# 08_FPGA.net
KiCad netlist of a schematic drawn in Altium Designer
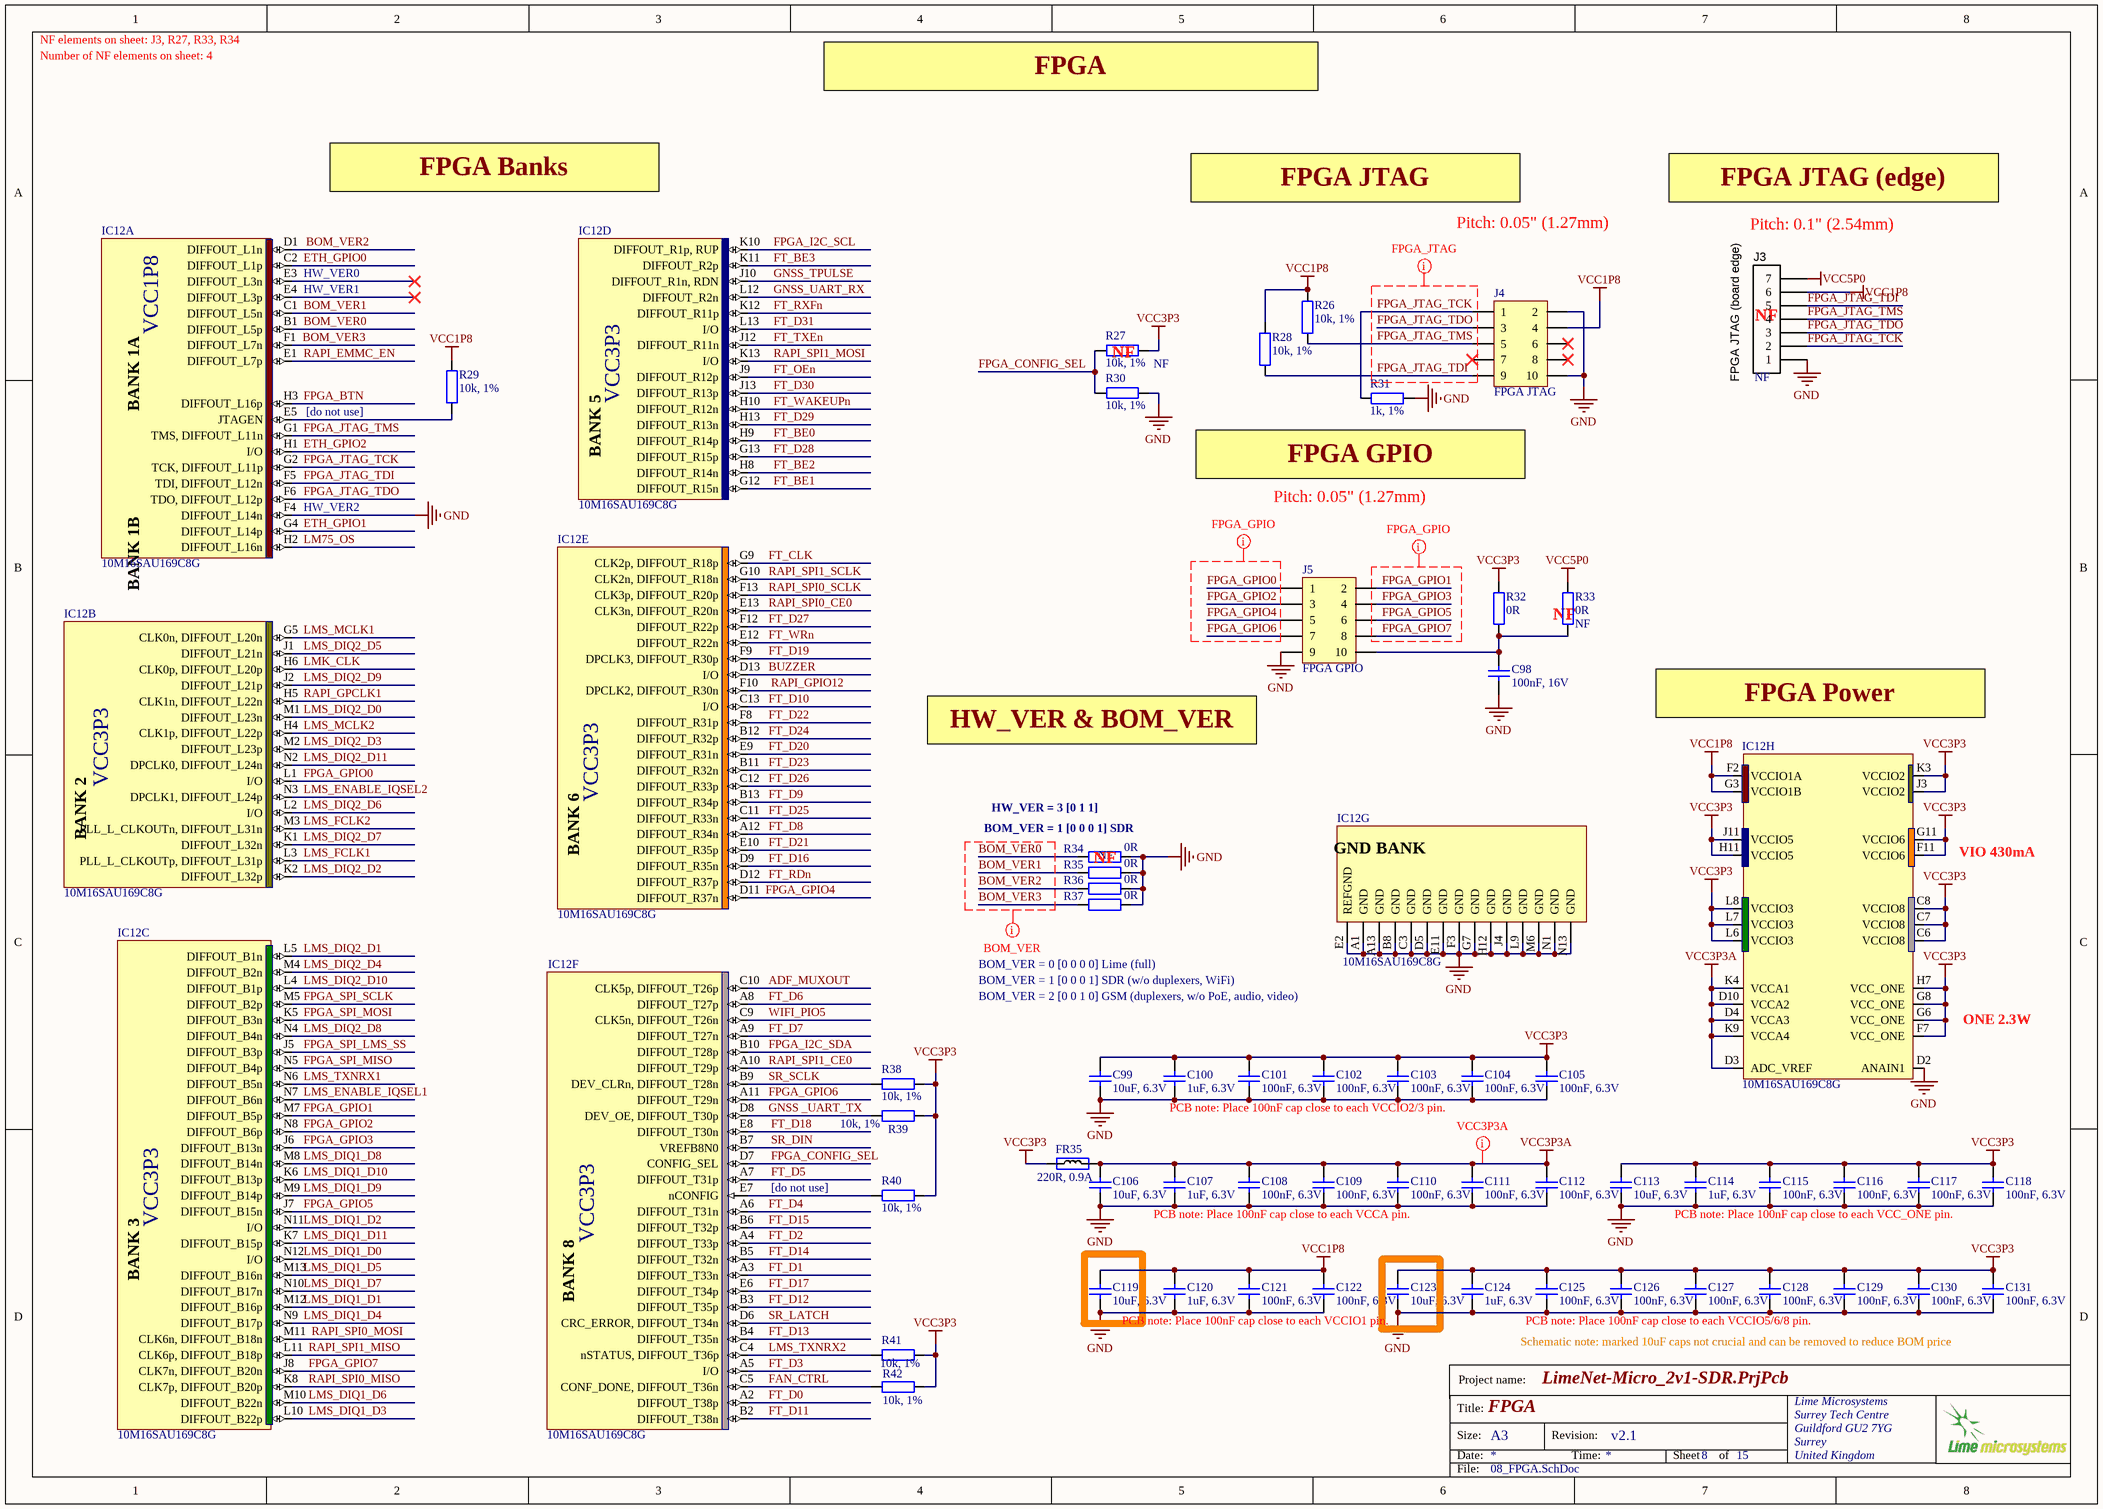
[diagram p0: 08_FPGA.SchDoc]

(export (version "E")
  (design (tool "Eeschema 10.0.6"))
  (components
    (comp (ref "C98")
      (value "100nF, 16V")
      (footprint "CAP0402")
      (fields
        (field (name "MANUFACTURER") "Murata Electronics")
        (field (name "TOLERANCE") "10 %")
        (field (name "MANUFACTURER PART NUMBER") "GRM155R71C104KA88D")
      )
      (libsource (lib "LimeMicroAltiumLib_schLib") (part "Cap_0402"))
    )
    (comp (ref "C99")
      (value "10uF, 6.3V")
      (footprint "CAP0603")
      (fields (field (name "TOLERANCE") "±20%") (field (name "MANUFACTURER") "Yageo"))
      (libsource (lib "LimeFPGAboard_schLib") (part "Cap_0603"))
    )
    (comp (ref "C100")
      (value "1uF, 6.3V")
      (footprint "CAP0201")
      (fields (field (name "TOLERANCE") "±20%") (field (name "MANUFACTURER") "TDK Corporation"))
      (libsource (lib "LimeMicroAltiumLib_schLib") (part "Cap_0402"))
    )
    (comp (ref "C101")
      (value "100nF, 6.3V")
      (footprint "CAP0201")
      (fields (field (name "MANUFACTURER") "Murata") (field (name "TOLERANCE") "10 %"))
      (libsource (lib "LimeMicroAltiumLib_schLib") (part "Cap_0402"))
    )
    (comp (ref "C102")
      (value "100nF, 6.3V")
      (footprint "CAP0201")
      (fields (field (name "MANUFACTURER") "Murata") (field (name "TOLERANCE") "10 %"))
      (libsource (lib "LimeMicroAltiumLib_schLib") (part "Cap_0402"))
    )
    (comp (ref "C103")
      (value "100nF, 6.3V")
      (footprint "CAP0201")
      (fields (field (name "MANUFACTURER") "Murata") (field (name "TOLERANCE") "10 %"))
      (libsource (lib "LimeMicroAltiumLib_schLib") (part "Cap_0402"))
    )
    (comp (ref "C104")
      (value "100nF, 6.3V")
      (footprint "CAP0201")
      (fields (field (name "MANUFACTURER") "Murata") (field (name "TOLERANCE") "10 %"))
      (libsource (lib "LimeMicroAltiumLib_schLib") (part "Cap_0402"))
    )
    (comp (ref "C105")
      (value "100nF, 6.3V")
      (footprint "CAP0201")
      (fields (field (name "MANUFACTURER") "Murata") (field (name "TOLERANCE") "10 %"))
      (libsource (lib "LimeMicroAltiumLib_schLib") (part "Cap_0402"))
    )
    (comp (ref "C106")
      (value "10uF, 6.3V")
      (footprint "CAP0603")
      (fields (field (name "TOLERANCE") "±20%") (field (name "MANUFACTURER") "Yageo"))
      (libsource (lib "LimeFPGAboard_schLib") (part "Cap_0603"))
    )
    (comp (ref "C107")
      (value "1uF, 6.3V")
      (footprint "CAP0201")
      (fields (field (name "TOLERANCE") "±20%") (field (name "MANUFACTURER") "TDK Corporation"))
      (libsource (lib "LimeMicroAltiumLib_schLib") (part "Cap_0402"))
    )
    (comp (ref "C108")
      (value "100nF, 6.3V")
      (footprint "CAP0201")
      (fields (field (name "MANUFACTURER") "Murata") (field (name "TOLERANCE") "10 %"))
      (libsource (lib "LimeMicroAltiumLib_schLib") (part "Cap_0402"))
    )
    (comp (ref "C109")
      (value "100nF, 6.3V")
      (footprint "CAP0201")
      (fields (field (name "MANUFACTURER") "Murata") (field (name "TOLERANCE") "10 %"))
      (libsource (lib "LimeMicroAltiumLib_schLib") (part "Cap_0402"))
    )
    (comp (ref "C110")
      (value "100nF, 6.3V")
      (footprint "CAP0201")
      (fields (field (name "MANUFACTURER") "Murata") (field (name "TOLERANCE") "10 %"))
      (libsource (lib "LimeMicroAltiumLib_schLib") (part "Cap_0402"))
    )
    (comp (ref "C111")
      (value "100nF, 6.3V")
      (footprint "CAP0201")
      (fields (field (name "MANUFACTURER") "Murata") (field (name "TOLERANCE") "10 %"))
      (libsource (lib "LimeMicroAltiumLib_schLib") (part "Cap_0402"))
    )
    (comp (ref "C112")
      (value "100nF, 6.3V")
      (footprint "CAP0201")
      (fields (field (name "MANUFACTURER") "Murata") (field (name "TOLERANCE") "10 %"))
      (libsource (lib "LimeMicroAltiumLib_schLib") (part "Cap_0402"))
    )
    (comp (ref "C113")
      (value "10uF, 6.3V")
      (footprint "CAP0603")
      (fields (field (name "TOLERANCE") "±20%") (field (name "MANUFACTURER") "Yageo"))
      (libsource (lib "LimeFPGAboard_schLib") (part "Cap_0603"))
    )
    (comp (ref "C114")
      (value "1uF, 6.3V")
      (footprint "CAP0201")
      (fields (field (name "TOLERANCE") "±20%") (field (name "MANUFACTURER") "TDK Corporation"))
      (libsource (lib "LimeMicroAltiumLib_schLib") (part "Cap_0402"))
    )
    (comp (ref "C115")
      (value "100nF, 6.3V")
      (footprint "CAP0201")
      (fields (field (name "MANUFACTURER") "Murata") (field (name "TOLERANCE") "10 %"))
      (libsource (lib "LimeMicroAltiumLib_schLib") (part "Cap_0402"))
    )
    (comp (ref "C116")
      (value "100nF, 6.3V")
      (footprint "CAP0201")
      (fields (field (name "MANUFACTURER") "Murata") (field (name "TOLERANCE") "10 %"))
      (libsource (lib "LimeMicroAltiumLib_schLib") (part "Cap_0402"))
    )
    (comp (ref "C117")
      (value "100nF, 6.3V")
      (footprint "CAP0201")
      (fields (field (name "MANUFACTURER") "Murata") (field (name "TOLERANCE") "10 %"))
      (libsource (lib "LimeMicroAltiumLib_schLib") (part "Cap_0402"))
    )
    (comp (ref "C118")
      (value "100nF, 6.3V")
      (footprint "CAP0201")
      (fields (field (name "MANUFACTURER") "Murata") (field (name "TOLERANCE") "10 %"))
      (libsource (lib "LimeMicroAltiumLib_schLib") (part "Cap_0402"))
    )
    (comp (ref "C119")
      (value "10uF, 6.3V")
      (footprint "CAP0603")
      (fields (field (name "TOLERANCE") "±20%") (field (name "MANUFACTURER") "Yageo"))
      (libsource (lib "LimeFPGAboard_schLib") (part "Cap_0603"))
    )
    (comp (ref "C120")
      (value "1uF, 6.3V")
      (footprint "CAP0201")
      (fields (field (name "TOLERANCE") "±20%") (field (name "MANUFACTURER") "TDK Corporation"))
      (libsource (lib "LimeMicroAltiumLib_schLib") (part "Cap_0402"))
    )
    (comp (ref "C121")
      (value "100nF, 6.3V")
      (footprint "CAP0201")
      (fields (field (name "MANUFACTURER") "Murata") (field (name "TOLERANCE") "10 %"))
      (libsource (lib "LimeMicroAltiumLib_schLib") (part "Cap_0402"))
    )
    (comp (ref "C122")
      (value "100nF, 6.3V")
      (footprint "CAP0201")
      (fields (field (name "MANUFACTURER") "Murata") (field (name "TOLERANCE") "10 %"))
      (libsource (lib "LimeMicroAltiumLib_schLib") (part "Cap_0402"))
    )
    (comp (ref "C123")
      (value "10uF, 6.3V")
      (footprint "CAP0603")
      (fields (field (name "TOLERANCE") "±20%") (field (name "MANUFACTURER") "Yageo"))
      (libsource (lib "LimeFPGAboard_schLib") (part "Cap_0603"))
    )
    (comp (ref "C124")
      (value "1uF, 6.3V")
      (footprint "CAP0201")
      (fields (field (name "TOLERANCE") "±20%") (field (name "MANUFACTURER") "TDK Corporation"))
      (libsource (lib "LimeMicroAltiumLib_schLib") (part "Cap_0402"))
    )
    (comp (ref "C125")
      (value "100nF, 6.3V")
      (footprint "CAP0201")
      (fields (field (name "MANUFACTURER") "Murata") (field (name "TOLERANCE") "10 %"))
      (libsource (lib "LimeMicroAltiumLib_schLib") (part "Cap_0402"))
    )
    (comp (ref "C126")
      (value "100nF, 6.3V")
      (footprint "CAP0201")
      (fields (field (name "MANUFACTURER") "Murata") (field (name "TOLERANCE") "10 %"))
      (libsource (lib "LimeMicroAltiumLib_schLib") (part "Cap_0402"))
    )
    (comp (ref "C127")
      (value "100nF, 6.3V")
      (footprint "CAP0201")
      (fields (field (name "MANUFACTURER") "Murata") (field (name "TOLERANCE") "10 %"))
      (libsource (lib "LimeMicroAltiumLib_schLib") (part "Cap_0402"))
    )
    (comp (ref "C128")
      (value "100nF, 6.3V")
      (footprint "CAP0201")
      (fields (field (name "MANUFACTURER") "Murata") (field (name "TOLERANCE") "10 %"))
      (libsource (lib "LimeMicroAltiumLib_schLib") (part "Cap_0402"))
    )
    (comp (ref "C129")
      (value "100nF, 6.3V")
      (footprint "CAP0201")
      (fields (field (name "MANUFACTURER") "Murata") (field (name "TOLERANCE") "10 %"))
      (libsource (lib "LimeMicroAltiumLib_schLib") (part "Cap_0402"))
    )
    (comp (ref "C130")
      (value "100nF, 6.3V")
      (footprint "CAP0201")
      (fields (field (name "MANUFACTURER") "Murata") (field (name "TOLERANCE") "10 %"))
      (libsource (lib "LimeMicroAltiumLib_schLib") (part "Cap_0402"))
    )
    (comp (ref "C131")
      (value "100nF, 6.3V")
      (footprint "CAP0201")
      (fields (field (name "MANUFACTURER") "Murata") (field (name "TOLERANCE") "10 %"))
      (libsource (lib "LimeMicroAltiumLib_schLib") (part "Cap_0402"))
    )
    (comp (ref "FR35")
      (value "220R, 0.9A")
      (footprint "RES0402")
      (fields (field (name "MANUFACTURER") "TDK Corporation"))
      (libsource (lib "LimeFPGAboard_schLib") (part "Ferrite"))
    )
    (comp (ref "IC12")
      (value "10M16SAU169C8G")
      (footprint "10M16SAU169C8G")
      (fields (field (name "MANUFACTURER") "Altera"))
      (libsource (lib "") (part "10M16SAU169C8G_1"))
    )
    (comp (ref "J3")
      (value "FPGA JTAG (board edge)")
      (footprint "Header7x1_TH")
      (description "Header, 7-pin")
      (fields (field (name "MANUFACTURER") "Sullins Connector Solutions") (field (name "ASSEMBLY INFO") "NF"))
      (libsource (lib "LimeMicroAltiumLib_schLib") (part "Header7P"))
    )
    (comp (ref "J4")
      (value "FPGA JTAG")
      (footprint "SWD_10_pin")
      (description "Header, 5-Pin, Dual row")
      (fields (field (name "MANUFACTURER") "Harwin Inc"))
      (libsource (lib "LimeMicroAltiumLib_schLib") (part "Header 5X2_SWD"))
    )
    (comp (ref "J5")
      (value "FPGA GPIO")
      (footprint "SWD_10_pin")
      (description "Header, 5-Pin, Dual row")
      (fields (field (name "MANUFACTURER") "Harwin Inc"))
      (libsource (lib "LimeMicroAltiumLib_schLib") (part "Header 5X2_SWD"))
    )
    (comp (ref "R26")
      (value "10k, 1%")
      (footprint "RES0402")
      (fields (field (name "MANUFACTURER") "Yageo") (field (name "TOLERANCE") "±1%"))
      (libsource (lib "LimeMicroAltiumLib_schLib") (part "Res_0402"))
    )
    (comp (ref "R27")
      (value "10k, 1%")
      (footprint "RES0402")
      (fields
        (field (name "ASSEMBLY INFO") "NF")
        (field (name "MANUFACTURER") "Yageo")
        (field (name "TOLERANCE") "±1%")
      )
      (libsource (lib "LimeMicroAltiumLib_schLib") (part "Res_0402"))
    )
    (comp (ref "R28")
      (value "10k, 1%")
      (footprint "RES0402")
      (fields (field (name "MANUFACTURER") "Yageo") (field (name "TOLERANCE") "±1%"))
      (libsource (lib "LimeMicroAltiumLib_schLib") (part "Res_0402"))
    )
    (comp (ref "R29")
      (value "10k, 1%")
      (footprint "RES0402")
      (fields (field (name "MANUFACTURER") "Yageo") (field (name "TOLERANCE") "±1%"))
      (libsource (lib "LimeMicroAltiumLib_schLib") (part "Res_0402"))
    )
    (comp (ref "R30")
      (value "10k, 1%")
      (footprint "RES0402")
      (fields (field (name "MANUFACTURER") "Yageo") (field (name "TOLERANCE") "±1%"))
      (libsource (lib "LimeMicroAltiumLib_schLib") (part "Res_0402"))
    )
    (comp (ref "R31")
      (value "1k, 1%")
      (footprint "RES0402")
      (fields (field (name "MANUFACTURER") "Stackpole Electronics Inc") (field (name "TOLERANCE") "±1%"))
      (libsource (lib "LimeMicroAltiumLib_schLib") (part "Res_0402"))
    )
    (comp (ref "R32")
      (value "0R")
      (footprint "RES0402")
      (fields (field (name "MANUFACTURER") "Yageo") (field (name "TOLERANCE") "Jumper"))
      (libsource (lib "LimeFPGAboard_schLib") (part "Res_0402"))
    )
    (comp (ref "R33")
      (value "0R")
      (footprint "RES0402")
      (fields
        (field (name "MANUFACTURER") "Yageo")
        (field (name "ASSEMBLY INFO") "NF")
        (field (name "TOLERANCE") "Jumper")
      )
      (libsource (lib "LimeFPGAboard_schLib") (part "Res_0402"))
    )
    (comp (ref "R34")
      (value "0R")
      (footprint "RES0402")
      (fields
        (field (name "MANUFACTURER") "Yageo")
        (field (name "ASSEMBLY INFO") "NF")
        (field (name "TOLERANCE") "Jumper")
      )
      (libsource (lib "LimeFPGAboard_schLib") (part "Res_0402"))
    )
    (comp (ref "R35")
      (value "0R")
      (footprint "RES0402")
      (fields (field (name "MANUFACTURER") "Yageo") (field (name "TOLERANCE") "Jumper"))
      (libsource (lib "LimeFPGAboard_schLib") (part "Res_0402"))
    )
    (comp (ref "R36")
      (value "0R")
      (footprint "RES0402")
      (fields (field (name "MANUFACTURER") "Yageo") (field (name "TOLERANCE") "Jumper"))
      (libsource (lib "LimeFPGAboard_schLib") (part "Res_0402"))
    )
    (comp (ref "R37")
      (value "0R")
      (footprint "RES0402")
      (fields (field (name "MANUFACTURER") "Yageo") (field (name "TOLERANCE") "Jumper"))
      (libsource (lib "LimeFPGAboard_schLib") (part "Res_0402"))
    )
    (comp (ref "R38")
      (value "10k, 1%")
      (footprint "RES0402")
      (fields (field (name "MANUFACTURER") "Yageo") (field (name "TOLERANCE") "±1%"))
      (libsource (lib "LimeMicroAltiumLib_schLib") (part "Res_0402"))
    )
    (comp (ref "R39")
      (value "10k, 1%")
      (footprint "RES0402")
      (fields (field (name "MANUFACTURER") "Yageo") (field (name "TOLERANCE") "±1%"))
      (libsource (lib "LimeMicroAltiumLib_schLib") (part "Res_0402"))
    )
    (comp (ref "R40")
      (value "10k, 1%")
      (footprint "RES0402")
      (fields (field (name "MANUFACTURER") "Yageo") (field (name "TOLERANCE") "±1%"))
      (libsource (lib "LimeMicroAltiumLib_schLib") (part "Res_0402"))
    )
    (comp (ref "R41")
      (value "10k, 1%")
      (footprint "RES0402")
      (fields (field (name "MANUFACTURER") "Yageo") (field (name "TOLERANCE") "±1%"))
      (libsource (lib "LimeMicroAltiumLib_schLib") (part "Res_0402"))
    )
    (comp (ref "R42")
      (value "10k, 1%")
      (footprint "RES0402")
      (fields (field (name "MANUFACTURER") "Yageo") (field (name "TOLERANCE") "±1%"))
      (libsource (lib "LimeMicroAltiumLib_schLib") (part "Res_0402"))
    )
  )
  (nets
    (net (code "1") (name "/ADF_MUXOUT") (class "Default")
      (node (ref "IC12") (pin "C10") (pinfunction "CLK5p,_DIFFOUT_T26p_C10") (pintype "bidirectional"))
    )
    (net (code "2") (name "/BOM_VER0") (class "Default")
      (node (ref "IC12") (pin "B1") (pinfunction "DIFFOUT_L5p_B1") (pintype "bidirectional"))
      (node (ref "R34") (pin "2") (pinfunction "2_2") (pintype "passive"))
    )
    (net (code "3") (name "/BOM_VER1") (class "Default")
      (node (ref "IC12") (pin "C1") (pinfunction "DIFFOUT_L5n_C1") (pintype "bidirectional"))
      (node (ref "R35") (pin "2") (pinfunction "2_2") (pintype "passive"))
    )
    (net (code "4") (name "/BOM_VER2") (class "Default")
      (node (ref "IC12") (pin "D1") (pinfunction "DIFFOUT_L1n_D1") (pintype "bidirectional"))
      (node (ref "R36") (pin "2") (pinfunction "2_2") (pintype "passive"))
    )
    (net (code "5") (name "/BOM_VER3") (class "Default")
      (node (ref "IC12") (pin "F1") (pinfunction "DIFFOUT_L7n_F1") (pintype "bidirectional"))
      (node (ref "R37") (pin "2") (pinfunction "2_2") (pintype "passive"))
    )
    (net (code "6") (name "/BUZZER") (class "Default")
      (node (ref "IC12") (pin "D13") (pinfunction "I/O_D13") (pintype "bidirectional"))
    )
    (net (code "7") (name "/ETH_GPIO0") (class "Default")
      (node (ref "IC12") (pin "C2") (pinfunction "DIFFOUT_L1p_C2") (pintype "bidirectional"))
    )
    (net (code "8") (name "/ETH_GPIO1") (class "Default")
      (node (ref "IC12") (pin "G4") (pinfunction "DIFFOUT_L14p_G4") (pintype "bidirectional"))
    )
    (net (code "9") (name "/ETH_GPIO2") (class "Default")
      (node (ref "IC12") (pin "H1") (pinfunction "I/O_H1") (pintype "bidirectional"))
    )
    (net (code "10") (name "/FAN_CTRL") (class "Default")
      (node (ref "IC12") (pin "C5") (pinfunction "CONF_DONE,_DIFFOUT_T36n_C5") (pintype "bidirectional"))
      (node (ref "R42") (pin "2") (pinfunction "2_2") (pintype "passive"))
    )
    (net (code "11") (name "/FPGA_BTN") (class "Default")
      (node (ref "IC12") (pin "H3") (pinfunction "DIFFOUT_L16p_H3") (pintype "bidirectional"))
    )
    (net (code "12") (name "/FPGA_CONFIG_SEL") (class "Default")
      (node (ref "IC12") (pin "D7") (pinfunction "CONFIG_SEL_D7") (pintype "bidirectional"))
      (node (ref "R27") (pin "2") (pinfunction "2_2") (pintype "passive"))
      (node (ref "R30") (pin "2") (pinfunction "2_2") (pintype "passive"))
    )
    (net (code "13") (name "/FPGA_GPIO0") (class "Default")
      (node (ref "IC12") (pin "L1") (pinfunction "I/O_L1") (pintype "bidirectional"))
      (node (ref "J5") (pin "1") (pinfunction "1_1") (pintype "passive"))
    )
    (net (code "14") (name "/FPGA_GPIO1") (class "Default")
      (node (ref "IC12") (pin "M7") (pinfunction "DIFFOUT_B5p_M7") (pintype "bidirectional"))
      (node (ref "J5") (pin "2") (pinfunction "2_2") (pintype "passive"))
    )
    (net (code "15") (name "/FPGA_GPIO2") (class "Default")
      (node (ref "IC12") (pin "N8") (pinfunction "DIFFOUT_B6p_N8") (pintype "bidirectional"))
      (node (ref "J5") (pin "3") (pinfunction "3_3") (pintype "passive"))
    )
    (net (code "16") (name "/FPGA_GPIO3") (class "Default")
      (node (ref "IC12") (pin "J6") (pinfunction "DIFFOUT_B13n_J6") (pintype "bidirectional"))
      (node (ref "J5") (pin "4") (pinfunction "4_4") (pintype "passive"))
    )
    (net (code "17") (name "/FPGA_GPIO4") (class "Default")
      (node (ref "IC12") (pin "D11") (pinfunction "DIFFOUT_R37n_D11") (pintype "bidirectional"))
      (node (ref "J5") (pin "5") (pinfunction "5_5") (pintype "passive"))
    )
    (net (code "18") (name "/FPGA_GPIO5") (class "Default")
      (node (ref "IC12") (pin "J7") (pinfunction "DIFFOUT_B15n_J7") (pintype "bidirectional"))
      (node (ref "J5") (pin "6") (pinfunction "6_6") (pintype "passive"))
    )
    (net (code "19") (name "/FPGA_GPIO6") (class "Default")
      (node (ref "IC12") (pin "A11") (pinfunction "DIFFOUT_T29n_A11") (pintype "bidirectional"))
      (node (ref "J5") (pin "7") (pinfunction "7_7") (pintype "passive"))
    )
    (net (code "20") (name "/FPGA_GPIO7") (class "Default")
      (node (ref "IC12") (pin "J8") (pinfunction "CLK7n,_DIFFOUT_B20n_J8") (pintype "bidirectional"))
      (node (ref "J5") (pin "8") (pinfunction "8_8") (pintype "passive"))
    )
    (net (code "21") (name "/FPGA_I2C_SCL") (class "Default")
      (node (ref "IC12") (pin "K10") (pinfunction "DIFFOUT_R1p,_RUP_K10") (pintype "bidirectional"))
    )
    (net (code "22") (name "/FPGA_I2C_SDA") (class "Default")
      (node (ref "IC12") (pin "B10") (pinfunction "DIFFOUT_T28p_B10") (pintype "bidirectional"))
    )
    (net (code "23") (name "/FPGA_JTAG_TCK") (class "Default")
      (node (ref "IC12") (pin "G2") (pinfunction "TCK,_DIFFOUT_L11p_G2") (pintype "bidirectional"))
      (node (ref "J3") (pin "2") (pinfunction "2_2") (pintype "passive"))
      (node (ref "J4") (pin "1") (pinfunction "1_1") (pintype "passive"))
      (node (ref "R31") (pin "1") (pinfunction "1_1") (pintype "passive"))
    )
    (net (code "24") (name "/FPGA_JTAG_TDI") (class "Default")
      (node (ref "IC12") (pin "F5") (pinfunction "TDI,_DIFFOUT_L12n_F5") (pintype "bidirectional"))
      (node (ref "J3") (pin "5") (pinfunction "5_5") (pintype "passive"))
      (node (ref "J4") (pin "9") (pinfunction "9_9") (pintype "passive"))
      (node (ref "R28") (pin "1") (pinfunction "1_1") (pintype "passive"))
    )
    (net (code "25") (name "/FPGA_JTAG_TDO") (class "Default")
      (node (ref "IC12") (pin "F6") (pinfunction "TDO,_DIFFOUT_L12p_F6") (pintype "bidirectional"))
      (node (ref "J3") (pin "3") (pinfunction "3_3") (pintype "passive"))
      (node (ref "J4") (pin "3") (pinfunction "3_3") (pintype "passive"))
    )
    (net (code "26") (name "/FPGA_JTAG_TMS") (class "Default")
      (node (ref "IC12") (pin "G1") (pinfunction "TMS,_DIFFOUT_L11n_G1") (pintype "bidirectional"))
      (node (ref "J3") (pin "4") (pinfunction "4_4") (pintype "passive"))
      (node (ref "J4") (pin "5") (pinfunction "5_5") (pintype "passive"))
      (node (ref "R26") (pin "1") (pinfunction "1_1") (pintype "passive"))
    )
    (net (code "27") (name "/FPGA_SPI_LMS_SS") (class "Default")
      (node (ref "IC12") (pin "J5") (pinfunction "DIFFOUT_B3p_J5") (pintype "bidirectional"))
    )
    (net (code "28") (name "/FPGA_SPI_MISO") (class "Default")
      (node (ref "IC12") (pin "N5") (pinfunction "DIFFOUT_B4p_N5") (pintype "bidirectional"))
    )
    (net (code "29") (name "/FPGA_SPI_MOSI") (class "Default")
      (node (ref "IC12") (pin "K5") (pinfunction "DIFFOUT_B3n_K5") (pintype "bidirectional"))
    )
    (net (code "30") (name "/FPGA_SPI_SCLK") (class "Default")
      (node (ref "IC12") (pin "M5") (pinfunction "DIFFOUT_B2p_M5") (pintype "bidirectional"))
    )
    (net (code "31") (name "/FT_BE0") (class "Default")
      (node (ref "IC12") (pin "H9") (pinfunction "DIFFOUT_R14p_H9") (pintype "bidirectional"))
    )
    (net (code "32") (name "/FT_BE1") (class "Default")
      (node (ref "IC12") (pin "G12") (pinfunction "DIFFOUT_R15n_G12") (pintype "bidirectional"))
    )
    (net (code "33") (name "/FT_BE2") (class "Default")
      (node (ref "IC12") (pin "H8") (pinfunction "DIFFOUT_R14n_H8") (pintype "bidirectional"))
    )
    (net (code "34") (name "/FT_BE3") (class "Default")
      (node (ref "IC12") (pin "K11") (pinfunction "DIFFOUT_R2p_K11") (pintype "bidirectional"))
    )
    (net (code "35") (name "/FT_CLK") (class "Default")
      (node (ref "IC12") (pin "G9") (pinfunction "CLK2p,_DIFFOUT_R18p_G9") (pintype "bidirectional"))
    )
    (net (code "36") (name "/FT_D0") (class "Default")
      (node (ref "IC12") (pin "A2") (pinfunction "DIFFOUT_T38p_A2") (pintype "bidirectional"))
    )
    (net (code "37") (name "/FT_D1") (class "Default")
      (node (ref "IC12") (pin "A3") (pinfunction "DIFFOUT_T33n_A3") (pintype "bidirectional"))
    )
    (net (code "38") (name "/FT_D2") (class "Default")
      (node (ref "IC12") (pin "A4") (pinfunction "DIFFOUT_T33p_A4") (pintype "bidirectional"))
    )
    (net (code "39") (name "/FT_D3") (class "Default")
      (node (ref "IC12") (pin "A5") (pinfunction "I/O_A5") (pintype "bidirectional"))
    )
    (net (code "40") (name "/FT_D4") (class "Default")
      (node (ref "IC12") (pin "A6") (pinfunction "DIFFOUT_T31n_A6") (pintype "bidirectional"))
    )
    (net (code "41") (name "/FT_D5") (class "Default")
      (node (ref "IC12") (pin "A7") (pinfunction "DIFFOUT_T31p_A7") (pintype "bidirectional"))
    )
    (net (code "42") (name "/FT_D6") (class "Default")
      (node (ref "IC12") (pin "A8") (pinfunction "DIFFOUT_T27p_A8") (pintype "bidirectional"))
    )
    (net (code "43") (name "/FT_D7") (class "Default")
      (node (ref "IC12") (pin "A9") (pinfunction "DIFFOUT_T27n_A9") (pintype "bidirectional"))
    )
    (net (code "44") (name "/FT_D8") (class "Default")
      (node (ref "IC12") (pin "A12") (pinfunction "DIFFOUT_R34n_A12") (pintype "bidirectional"))
    )
    (net (code "45") (name "/FT_D9") (class "Default")
      (node (ref "IC12") (pin "B13") (pinfunction "DIFFOUT_R34p_B13") (pintype "bidirectional"))
    )
    (net (code "46") (name "/FT_D10") (class "Default")
      (node (ref "IC12") (pin "C13") (pinfunction "I/O_C13") (pintype "bidirectional"))
    )
    (net (code "47") (name "/FT_D11") (class "Default")
      (node (ref "IC12") (pin "B2") (pinfunction "DIFFOUT_T38n_B2") (pintype "bidirectional"))
    )
    (net (code "48") (name "/FT_D12") (class "Default")
      (node (ref "IC12") (pin "B3") (pinfunction "DIFFOUT_T35p_B3") (pintype "bidirectional"))
    )
    (net (code "49") (name "/FT_D13") (class "Default")
      (node (ref "IC12") (pin "B4") (pinfunction "DIFFOUT_T35n_B4") (pintype "bidirectional"))
    )
    (net (code "50") (name "/FT_D14") (class "Default")
      (node (ref "IC12") (pin "B5") (pinfunction "DIFFOUT_T32n_B5") (pintype "bidirectional"))
    )
    (net (code "51") (name "/FT_D15") (class "Default")
      (node (ref "IC12") (pin "B6") (pinfunction "DIFFOUT_T32p_B6") (pintype "bidirectional"))
    )
    (net (code "52") (name "/FT_D16") (class "Default")
      (node (ref "IC12") (pin "D9") (pinfunction "DIFFOUT_R35n_D9") (pintype "bidirectional"))
    )
    (net (code "53") (name "/FT_D17") (class "Default")
      (node (ref "IC12") (pin "E6") (pinfunction "DIFFOUT_T34p_E6") (pintype "bidirectional"))
    )
    (net (code "54") (name "/FT_D18") (class "Default")
      (node (ref "IC12") (pin "E8") (pinfunction "DIFFOUT_T30n_E8") (pintype "bidirectional"))
    )
    (net (code "55") (name "/FT_D19") (class "Default")
      (node (ref "IC12") (pin "F9") (pinfunction "DPCLK3,_DIFFOUT_R30p_F9") (pintype "bidirectional"))
    )
    (net (code "56") (name "/FT_D20") (class "Default")
      (node (ref "IC12") (pin "E9") (pinfunction "DIFFOUT_R31n_E9") (pintype "bidirectional"))
    )
    (net (code "57") (name "/FT_D21") (class "Default")
      (node (ref "IC12") (pin "E10") (pinfunction "DIFFOUT_R35p_E10") (pintype "bidirectional"))
    )
    (net (code "58") (name "/FT_D22") (class "Default")
      (node (ref "IC12") (pin "F8") (pinfunction "DIFFOUT_R31p_F8") (pintype "bidirectional"))
    )
    (net (code "59") (name "/FT_D23") (class "Default")
      (node (ref "IC12") (pin "B11") (pinfunction "DIFFOUT_R32n_B11") (pintype "bidirectional"))
    )
    (net (code "60") (name "/FT_D24") (class "Default")
      (node (ref "IC12") (pin "B12") (pinfunction "DIFFOUT_R32p_B12") (pintype "bidirectional"))
    )
    (net (code "61") (name "/FT_D25") (class "Default")
      (node (ref "IC12") (pin "C11") (pinfunction "DIFFOUT_R33n_C11") (pintype "bidirectional"))
    )
    (net (code "62") (name "/FT_D26") (class "Default")
      (node (ref "IC12") (pin "C12") (pinfunction "DIFFOUT_R33p_C12") (pintype "bidirectional"))
    )
    (net (code "63") (name "/FT_D27") (class "Default")
      (node (ref "IC12") (pin "F12") (pinfunction "DIFFOUT_R22p_F12") (pintype "bidirectional"))
    )
    (net (code "64") (name "/FT_D28") (class "Default")
      (node (ref "IC12") (pin "G13") (pinfunction "DIFFOUT_R15p_G13") (pintype "bidirectional"))
    )
    (net (code "65") (name "/FT_D29") (class "Default")
      (node (ref "IC12") (pin "H13") (pinfunction "DIFFOUT_R13n_H13") (pintype "bidirectional"))
    )
    (net (code "66") (name "/FT_D30") (class "Default")
      (node (ref "IC12") (pin "J13") (pinfunction "DIFFOUT_R13p_J13") (pintype "bidirectional"))
    )
    (net (code "67") (name "/FT_D31") (class "Default")
      (node (ref "IC12") (pin "L13") (pinfunction "I/O_L13") (pintype "bidirectional"))
    )
    (net (code "68") (name "/FT_OEn") (class "Default")
      (node (ref "IC12") (pin "J9") (pinfunction "DIFFOUT_R12p_J9") (pintype "bidirectional"))
    )
    (net (code "69") (name "/FT_RDn") (class "Default")
      (node (ref "IC12") (pin "D12") (pinfunction "DIFFOUT_R37p_D12") (pintype "bidirectional"))
    )
    (net (code "70") (name "/FT_RXFn") (class "Default")
      (node (ref "IC12") (pin "K12") (pinfunction "DIFFOUT_R11p_K12") (pintype "bidirectional"))
    )
    (net (code "71") (name "/FT_TXEn") (class "Default")
      (node (ref "IC12") (pin "J12") (pinfunction "DIFFOUT_R11n_J12") (pintype "bidirectional"))
    )
    (net (code "72") (name "/FT_WAKEUPn") (class "Default")
      (node (ref "IC12") (pin "H10") (pinfunction "DIFFOUT_R12n_H10") (pintype "bidirectional"))
    )
    (net (code "73") (name "/FT_WRn") (class "Default")
      (node (ref "IC12") (pin "E12") (pinfunction "DIFFOUT_R22n_E12") (pintype "bidirectional"))
    )
    (net (code "74") (name "/GNSS _UART_TX") (class "Default")
      (node (ref "IC12") (pin "D8") (pinfunction "DEV_OE,_DIFFOUT_T30p_D8") (pintype "bidirectional"))
      (node (ref "R39") (pin "2") (pinfunction "2_2") (pintype "passive"))
    )
    (net (code "75") (name "/GNSS_TPULSE") (class "Default")
      (node (ref "IC12") (pin "J10") (pinfunction "DIFFOUT_R1n,_RDN_J10") (pintype "bidirectional"))
    )
    (net (code "76") (name "/GNSS_UART_RX") (class "Default")
      (node (ref "IC12") (pin "L12") (pinfunction "DIFFOUT_R2n_L12") (pintype "bidirectional"))
    )
    (net (code "77") (name "/LM75_OS") (class "Default")
      (node (ref "IC12") (pin "H2") (pinfunction "DIFFOUT_L16n_H2") (pintype "bidirectional"))
    )
    (net (code "78") (name "/LMK_CLK") (class "Default")
      (node (ref "IC12") (pin "H6") (pinfunction "CLK0p,_DIFFOUT_L20p_H6") (pintype "bidirectional"))
    )
    (net (code "79") (name "/LMS_DIQ1_D0") (class "Default")
      (node (ref "IC12") (pin "N12") (pinfunction "I/O_N12") (pintype "bidirectional"))
    )
    (net (code "80") (name "/LMS_DIQ1_D1") (class "Default")
      (node (ref "IC12") (pin "M12") (pinfunction "DIFFOUT_B16p_M12") (pintype "bidirectional"))
    )
    (net (code "81") (name "/LMS_DIQ1_D2") (class "Default")
      (node (ref "IC12") (pin "N11") (pinfunction "I/O_N11") (pintype "bidirectional"))
    )
    (net (code "82") (name "/LMS_DIQ1_D3") (class "Default")
      (node (ref "IC12") (pin "L10") (pinfunction "DIFFOUT_B22p_L10") (pintype "bidirectional"))
    )
    (net (code "83") (name "/LMS_DIQ1_D4") (class "Default")
      (node (ref "IC12") (pin "N9") (pinfunction "DIFFOUT_B17p_N9") (pintype "bidirectional"))
    )
    (net (code "84") (name "/LMS_DIQ1_D5") (class "Default")
      (node (ref "IC12") (pin "M13") (pinfunction "DIFFOUT_B16n_M13") (pintype "bidirectional"))
    )
    (net (code "85") (name "/LMS_DIQ1_D6") (class "Default")
      (node (ref "IC12") (pin "M10") (pinfunction "DIFFOUT_B22n_M10") (pintype "bidirectional"))
    )
    (net (code "86") (name "/LMS_DIQ1_D7") (class "Default")
      (node (ref "IC12") (pin "N10") (pinfunction "DIFFOUT_B17n_N10") (pintype "bidirectional"))
    )
    (net (code "87") (name "/LMS_DIQ1_D8") (class "Default")
      (node (ref "IC12") (pin "M8") (pinfunction "DIFFOUT_B14n_M8") (pintype "bidirectional"))
    )
    (net (code "88") (name "/LMS_DIQ1_D9") (class "Default")
      (node (ref "IC12") (pin "M9") (pinfunction "DIFFOUT_B14p_M9") (pintype "bidirectional"))
    )
    (net (code "89") (name "/LMS_DIQ1_D10") (class "Default")
      (node (ref "IC12") (pin "K6") (pinfunction "DIFFOUT_B13p_K6") (pintype "bidirectional"))
    )
    (net (code "90") (name "/LMS_DIQ1_D11") (class "Default")
      (node (ref "IC12") (pin "K7") (pinfunction "DIFFOUT_B15p_K7") (pintype "bidirectional"))
    )
    (net (code "91") (name "/LMS_DIQ2_D0") (class "Default")
      (node (ref "IC12") (pin "M1") (pinfunction "DIFFOUT_L23n_M1") (pintype "bidirectional"))
    )
    (net (code "92") (name "/LMS_DIQ2_D1") (class "Default")
      (node (ref "IC12") (pin "L5") (pinfunction "DIFFOUT_B1n_L5") (pintype "bidirectional"))
    )
    (net (code "93") (name "/LMS_DIQ2_D2") (class "Default")
      (node (ref "IC12") (pin "K2") (pinfunction "DIFFOUT_L32p_K2") (pintype "bidirectional"))
    )
    (net (code "94") (name "/LMS_DIQ2_D3") (class "Default")
      (node (ref "IC12") (pin "M2") (pinfunction "DIFFOUT_L23p_M2") (pintype "bidirectional"))
    )
    (net (code "95") (name "/LMS_DIQ2_D4") (class "Default")
      (node (ref "IC12") (pin "M4") (pinfunction "DIFFOUT_B2n_M4") (pintype "bidirectional"))
    )
    (net (code "96") (name "/LMS_DIQ2_D5") (class "Default")
      (node (ref "IC12") (pin "J1") (pinfunction "DIFFOUT_L21n_J1") (pintype "bidirectional"))
    )
    (net (code "97") (name "/LMS_DIQ2_D6") (class "Default")
      (node (ref "IC12") (pin "L2") (pinfunction "I/O_L2") (pintype "bidirectional"))
    )
    (net (code "98") (name "/LMS_DIQ2_D7") (class "Default")
      (node (ref "IC12") (pin "K1") (pinfunction "DIFFOUT_L32n_K1") (pintype "bidirectional"))
    )
    (net (code "99") (name "/LMS_DIQ2_D8") (class "Default")
      (node (ref "IC12") (pin "N4") (pinfunction "DIFFOUT_B4n_N4") (pintype "bidirectional"))
    )
    (net (code "100") (name "/LMS_DIQ2_D9") (class "Default")
      (node (ref "IC12") (pin "J2") (pinfunction "DIFFOUT_L21p_J2") (pintype "bidirectional"))
    )
    (net (code "101") (name "/LMS_DIQ2_D10") (class "Default")
      (node (ref "IC12") (pin "L4") (pinfunction "DIFFOUT_B1p_L4") (pintype "bidirectional"))
    )
    (net (code "102") (name "/LMS_DIQ2_D11") (class "Default")
      (node (ref "IC12") (pin "N2") (pinfunction "DPCLK0,_DIFFOUT_L24n_N2") (pintype "bidirectional"))
    )
    (net (code "103") (name "/LMS_ENABLE_IQSEL1") (class "Default")
      (node (ref "IC12") (pin "N7") (pinfunction "DIFFOUT_B6n_N7") (pintype "bidirectional"))
    )
    (net (code "104") (name "/LMS_ENABLE_IQSEL2") (class "Default")
      (node (ref "IC12") (pin "N3") (pinfunction "DPCLK1,_DIFFOUT_L24p_N3") (pintype "bidirectional"))
    )
    (net (code "105") (name "/LMS_FCLK1") (class "Default")
      (node (ref "IC12") (pin "L3") (pinfunction "PLL_L_CLKOUTp,_DIFFOUT_L31p_L3") (pintype "bidirectional"))
    )
    (net (code "106") (name "/LMS_FCLK2") (class "Default")
      (node (ref "IC12") (pin "M3") (pinfunction "PLL_L_CLKOUTn,_DIFFOUT_L31n_M3") (pintype "bidirectional"))
    )
    (net (code "107") (name "/LMS_MCLK1") (class "Default")
      (node (ref "IC12") (pin "G5") (pinfunction "CLK0n,_DIFFOUT_L20n_G5") (pintype "bidirectional"))
    )
    (net (code "108") (name "/LMS_MCLK2") (class "Default")
      (node (ref "IC12") (pin "H4") (pinfunction "CLK1p,_DIFFOUT_L22p_H4") (pintype "bidirectional"))
    )
    (net (code "109") (name "/LMS_TXNRX1") (class "Default")
      (node (ref "IC12") (pin "N6") (pinfunction "DIFFOUT_B5n_N6") (pintype "bidirectional"))
    )
    (net (code "110") (name "/LMS_TXNRX2") (class "Default")
      (node (ref "IC12") (pin "C4") (pinfunction "nSTATUS,_DIFFOUT_T36p_C4") (pintype "bidirectional"))
      (node (ref "R41") (pin "2") (pinfunction "2_2") (pintype "passive"))
    )
    (net (code "111") (name "/RAPI_EMMC_EN") (class "Default")
      (node (ref "IC12") (pin "E1") (pinfunction "DIFFOUT_L7p_E1") (pintype "bidirectional"))
    )
    (net (code "112") (name "/RAPI_GPCLK1") (class "Default")
      (node (ref "IC12") (pin "H5") (pinfunction "CLK1n,_DIFFOUT_L22n_H5") (pintype "bidirectional"))
    )
    (net (code "113") (name "/RAPI_GPIO12") (class "Default")
      (node (ref "IC12") (pin "F10") (pinfunction "DPCLK2,_DIFFOUT_R30n_F10") (pintype "bidirectional"))
    )
    (net (code "114") (name "/RAPI_SPI0_CE0") (class "Default")
      (node (ref "IC12") (pin "E13") (pinfunction "CLK3n,_DIFFOUT_R20n_E13") (pintype "bidirectional"))
    )
    (net (code "115") (name "/RAPI_SPI0_MISO") (class "Default")
      (node (ref "IC12") (pin "K8") (pinfunction "CLK7p,_DIFFOUT_B20p_K8") (pintype "bidirectional"))
    )
    (net (code "116") (name "/RAPI_SPI0_MOSI") (class "Default")
      (node (ref "IC12") (pin "M11") (pinfunction "CLK6n,_DIFFOUT_B18n_M11") (pintype "bidirectional"))
    )
    (net (code "117") (name "/RAPI_SPI0_SCLK") (class "Default")
      (node (ref "IC12") (pin "F13") (pinfunction "CLK3p,_DIFFOUT_R20p_F13") (pintype "bidirectional"))
    )
    (net (code "118") (name "/RAPI_SPI1_CE0") (class "Default")
      (node (ref "IC12") (pin "A10") (pinfunction "DIFFOUT_T29p_A10") (pintype "bidirectional"))
    )
    (net (code "119") (name "/RAPI_SPI1_MISO") (class "Default")
      (node (ref "IC12") (pin "L11") (pinfunction "CLK6p,_DIFFOUT_B18p_L11") (pintype "bidirectional"))
    )
    (net (code "120") (name "/RAPI_SPI1_MOSI") (class "Default")
      (node (ref "IC12") (pin "K13") (pinfunction "I/O_K13") (pintype "bidirectional"))
    )
    (net (code "121") (name "/RAPI_SPI1_SCLK") (class "Default")
      (node (ref "IC12") (pin "G10") (pinfunction "CLK2n,_DIFFOUT_R18n_G10") (pintype "bidirectional"))
    )
    (net (code "122") (name "/SR_DIN") (class "Default")
      (node (ref "IC12") (pin "B7") (pinfunction "VREFB8N0_B7") (pintype "bidirectional"))
    )
    (net (code "123") (name "/SR_LATCH") (class "Default")
      (node (ref "IC12") (pin "D6") (pinfunction "CRC_ERROR,_DIFFOUT_T34n_D6") (pintype "bidirectional"))
    )
    (net (code "124") (name "/SR_SCLK") (class "Default")
      (node (ref "IC12") (pin "B9") (pinfunction "DEV_CLRn,_DIFFOUT_T28n_B9") (pintype "bidirectional"))
      (node (ref "R38") (pin "2") (pinfunction "2_2") (pintype "passive"))
    )
    (net (code "125") (name "/WIFI_PIO5") (class "Default")
      (node (ref "IC12") (pin "C9") (pinfunction "CLK5n,_DIFFOUT_T26n_C9") (pintype "bidirectional"))
    )
    (net (code "126") (name "GND") (class "Default")
      (node (ref "C100") (pin "2") (pinfunction "2_2") (pintype "passive"))
      (node (ref "C101") (pin "2") (pinfunction "2_2") (pintype "passive"))
      (node (ref "C102") (pin "2") (pinfunction "2_2") (pintype "passive"))
      (node (ref "C103") (pin "2") (pinfunction "2_2") (pintype "passive"))
      (node (ref "C104") (pin "2") (pinfunction "2_2") (pintype "passive"))
      (node (ref "C105") (pin "2") (pinfunction "2_2") (pintype "passive"))
      (node (ref "C106") (pin "1") (pinfunction "1_1") (pintype "passive"))
      (node (ref "C107") (pin "2") (pinfunction "2_2") (pintype "passive"))
      (node (ref "C108") (pin "2") (pinfunction "2_2") (pintype "passive"))
      (node (ref "C109") (pin "2") (pinfunction "2_2") (pintype "passive"))
      (node (ref "C110") (pin "2") (pinfunction "2_2") (pintype "passive"))
      (node (ref "C111") (pin "2") (pinfunction "2_2") (pintype "passive"))
      (node (ref "C112") (pin "2") (pinfunction "2_2") (pintype "passive"))
      (node (ref "C113") (pin "1") (pinfunction "1_1") (pintype "passive"))
      (node (ref "C114") (pin "2") (pinfunction "2_2") (pintype "passive"))
      (node (ref "C115") (pin "2") (pinfunction "2_2") (pintype "passive"))
      (node (ref "C116") (pin "2") (pinfunction "2_2") (pintype "passive"))
      (node (ref "C117") (pin "2") (pinfunction "2_2") (pintype "passive"))
      (node (ref "C118") (pin "2") (pinfunction "2_2") (pintype "passive"))
      (node (ref "C119") (pin "1") (pinfunction "1_1") (pintype "passive"))
      (node (ref "C120") (pin "2") (pinfunction "2_2") (pintype "passive"))
      (node (ref "C121") (pin "2") (pinfunction "2_2") (pintype "passive"))
      (node (ref "C122") (pin "2") (pinfunction "2_2") (pintype "passive"))
      (node (ref "C123") (pin "1") (pinfunction "1_1") (pintype "passive"))
      (node (ref "C124") (pin "2") (pinfunction "2_2") (pintype "passive"))
      (node (ref "C125") (pin "2") (pinfunction "2_2") (pintype "passive"))
      (node (ref "C126") (pin "2") (pinfunction "2_2") (pintype "passive"))
      (node (ref "C127") (pin "2") (pinfunction "2_2") (pintype "passive"))
      (node (ref "C128") (pin "2") (pinfunction "2_2") (pintype "passive"))
      (node (ref "C129") (pin "2") (pinfunction "2_2") (pintype "passive"))
      (node (ref "C130") (pin "2") (pinfunction "2_2") (pintype "passive"))
      (node (ref "C131") (pin "2") (pinfunction "2_2") (pintype "passive"))
      (node (ref "C98") (pin "1") (pinfunction "1_1") (pintype "passive"))
      (node (ref "C99") (pin "1") (pinfunction "1_1") (pintype "passive"))
      (node (ref "IC12") (pin "A1") (pinfunction "GND_A1") (pintype "passive"))
      (node (ref "IC12") (pin "A13") (pinfunction "GND_A13") (pintype "passive"))
      (node (ref "IC12") (pin "B8") (pinfunction "GND_B8") (pintype "passive"))
      (node (ref "IC12") (pin "C3") (pinfunction "GND_C3") (pintype "passive"))
      (node (ref "IC12") (pin "D2") (pinfunction "ANAIN1_D2") (pintype "passive"))
      (node (ref "IC12") (pin "D5") (pinfunction "GND_D5") (pintype "passive"))
      (node (ref "IC12") (pin "E11") (pinfunction "GND_E11") (pintype "passive"))
      (node (ref "IC12") (pin "E2") (pinfunction "REFGND_E2") (pintype "passive"))
      (node (ref "IC12") (pin "F3") (pinfunction "GND_F3") (pintype "passive"))
      (node (ref "IC12") (pin "F4") (pinfunction "DIFFOUT_L14n_F4") (pintype "bidirectional"))
      (node (ref "IC12") (pin "G7") (pinfunction "GND_G7") (pintype "passive"))
      (node (ref "IC12") (pin "H12") (pinfunction "GND_H12") (pintype "passive"))
      (node (ref "IC12") (pin "J4") (pinfunction "GND_J4") (pintype "passive"))
      (node (ref "IC12") (pin "L9") (pinfunction "GND_L9") (pintype "passive"))
      (node (ref "IC12") (pin "M6") (pinfunction "GND_M6") (pintype "passive"))
      (node (ref "IC12") (pin "N1") (pinfunction "GND_N1") (pintype "passive"))
      (node (ref "IC12") (pin "N13") (pinfunction "GND_N13") (pintype "passive"))
      (node (ref "J3") (pin "1") (pinfunction "1_1") (pintype "passive"))
      (node (ref "J4") (pin "10") (pinfunction "10_10") (pintype "passive"))
      (node (ref "J4") (pin "2") (pinfunction "2_2") (pintype "passive"))
      (node (ref "J5") (pin "9") (pinfunction "9_9") (pintype "passive"))
      (node (ref "R30") (pin "1") (pinfunction "1_1") (pintype "passive"))
      (node (ref "R31") (pin "2") (pinfunction "2_2") (pintype "passive"))
      (node (ref "R34") (pin "1") (pinfunction "1_1") (pintype "passive"))
      (node (ref "R35") (pin "1") (pinfunction "1_1") (pintype "passive"))
      (node (ref "R36") (pin "1") (pinfunction "1_1") (pintype "passive"))
      (node (ref "R37") (pin "1") (pinfunction "1_1") (pintype "passive"))
    )
    (net (code "127") (name "Net-(C98-Pad2)") (class "Default")
      (node (ref "C98") (pin "2") (pinfunction "2_2") (pintype "passive"))
      (node (ref "J5") (pin "10") (pinfunction "10_10") (pintype "passive"))
      (node (ref "R32") (pin "2") (pinfunction "2_2") (pintype "passive"))
      (node (ref "R33") (pin "2") (pinfunction "2_2") (pintype "passive"))
    )
    (net (code "128") (name "Net-(IC12A-JTAGEN)") (class "Default")
      (node (ref "IC12") (pin "E5") (pinfunction "JTAGEN_E5") (pintype "bidirectional"))
      (node (ref "R29") (pin "2") (pinfunction "2_2") (pintype "passive"))
    )
    (net (code "129") (name "Net-(IC12F-nCONFIG)") (class "Default")
      (node (ref "IC12") (pin "E7") (pinfunction "nCONFIG_E7") (pintype "input"))
      (node (ref "R40") (pin "2") (pinfunction "2_2") (pintype "passive"))
    )
    (net (code "130") (name "VCC1P8") (class "Default")
      (node (ref "C119") (pin "2") (pinfunction "2_2") (pintype "passive"))
      (node (ref "C120") (pin "1") (pinfunction "1_1") (pintype "passive"))
      (node (ref "C121") (pin "1") (pinfunction "1_1") (pintype "passive"))
      (node (ref "C122") (pin "1") (pinfunction "1_1") (pintype "passive"))
      (node (ref "IC12") (pin "F2") (pinfunction "VCCIO1A_F2") (pintype "passive"))
      (node (ref "IC12") (pin "G3") (pinfunction "VCCIO1B_G3") (pintype "passive"))
      (node (ref "J3") (pin "6") (pinfunction "6_6") (pintype "passive"))
      (node (ref "J4") (pin "4") (pinfunction "4_4") (pintype "passive"))
      (node (ref "R26") (pin "2") (pinfunction "2_2") (pintype "passive"))
      (node (ref "R28") (pin "2") (pinfunction "2_2") (pintype "passive"))
      (node (ref "R29") (pin "1") (pinfunction "1_1") (pintype "passive"))
    )
    (net (code "131") (name "VCC3P3") (class "Default")
      (node (ref "C100") (pin "1") (pinfunction "1_1") (pintype "passive"))
      (node (ref "C101") (pin "1") (pinfunction "1_1") (pintype "passive"))
      (node (ref "C102") (pin "1") (pinfunction "1_1") (pintype "passive"))
      (node (ref "C103") (pin "1") (pinfunction "1_1") (pintype "passive"))
      (node (ref "C104") (pin "1") (pinfunction "1_1") (pintype "passive"))
      (node (ref "C105") (pin "1") (pinfunction "1_1") (pintype "passive"))
      (node (ref "C113") (pin "2") (pinfunction "2_2") (pintype "passive"))
      (node (ref "C114") (pin "1") (pinfunction "1_1") (pintype "passive"))
      (node (ref "C115") (pin "1") (pinfunction "1_1") (pintype "passive"))
      (node (ref "C116") (pin "1") (pinfunction "1_1") (pintype "passive"))
      (node (ref "C117") (pin "1") (pinfunction "1_1") (pintype "passive"))
      (node (ref "C118") (pin "1") (pinfunction "1_1") (pintype "passive"))
      (node (ref "C123") (pin "2") (pinfunction "2_2") (pintype "passive"))
      (node (ref "C124") (pin "1") (pinfunction "1_1") (pintype "passive"))
      (node (ref "C125") (pin "1") (pinfunction "1_1") (pintype "passive"))
      (node (ref "C126") (pin "1") (pinfunction "1_1") (pintype "passive"))
      (node (ref "C127") (pin "1") (pinfunction "1_1") (pintype "passive"))
      (node (ref "C128") (pin "1") (pinfunction "1_1") (pintype "passive"))
      (node (ref "C129") (pin "1") (pinfunction "1_1") (pintype "passive"))
      (node (ref "C130") (pin "1") (pinfunction "1_1") (pintype "passive"))
      (node (ref "C131") (pin "1") (pinfunction "1_1") (pintype "passive"))
      (node (ref "C99") (pin "2") (pinfunction "2_2") (pintype "passive"))
      (node (ref "FR35") (pin "1") (pinfunction "1_1") (pintype "passive"))
      (node (ref "IC12") (pin "C6") (pinfunction "VCCIO8_C6") (pintype "passive"))
      (node (ref "IC12") (pin "C7") (pinfunction "VCCIO8_C7") (pintype "passive"))
      (node (ref "IC12") (pin "C8") (pinfunction "VCCIO8_C8") (pintype "passive"))
      (node (ref "IC12") (pin "F11") (pinfunction "VCCIO6_F11") (pintype "passive"))
      (node (ref "IC12") (pin "F7") (pinfunction "VCC_ONE_F7") (pintype "passive"))
      (node (ref "IC12") (pin "G11") (pinfunction "VCCIO6_G11") (pintype "passive"))
      (node (ref "IC12") (pin "G6") (pinfunction "VCC_ONE_G6") (pintype "passive"))
      (node (ref "IC12") (pin "G8") (pinfunction "VCC_ONE_G8") (pintype "passive"))
      (node (ref "IC12") (pin "H11") (pinfunction "VCCIO5_H11") (pintype "passive"))
      (node (ref "IC12") (pin "H7") (pinfunction "VCC_ONE_H7") (pintype "passive"))
      (node (ref "IC12") (pin "J11") (pinfunction "VCCIO5_J11") (pintype "passive"))
      (node (ref "IC12") (pin "J3") (pinfunction "VCCIO2_J3") (pintype "passive"))
      (node (ref "IC12") (pin "K3") (pinfunction "VCCIO2_K3") (pintype "passive"))
      (node (ref "IC12") (pin "L6") (pinfunction "VCCIO3_L6") (pintype "passive"))
      (node (ref "IC12") (pin "L7") (pinfunction "VCCIO3_L7") (pintype "passive"))
      (node (ref "IC12") (pin "L8") (pinfunction "VCCIO3_L8") (pintype "passive"))
      (node (ref "R27") (pin "1") (pinfunction "1_1") (pintype "passive"))
      (node (ref "R32") (pin "1") (pinfunction "1_1") (pintype "passive"))
      (node (ref "R38") (pin "1") (pinfunction "1_1") (pintype "passive"))
      (node (ref "R39") (pin "1") (pinfunction "1_1") (pintype "passive"))
      (node (ref "R40") (pin "1") (pinfunction "1_1") (pintype "passive"))
      (node (ref "R41") (pin "1") (pinfunction "1_1") (pintype "passive"))
      (node (ref "R42") (pin "1") (pinfunction "1_1") (pintype "passive"))
    )
    (net (code "132") (name "VCC3P3A") (class "Default")
      (node (ref "C106") (pin "2") (pinfunction "2_2") (pintype "passive"))
      (node (ref "C107") (pin "1") (pinfunction "1_1") (pintype "passive"))
      (node (ref "C108") (pin "1") (pinfunction "1_1") (pintype "passive"))
      (node (ref "C109") (pin "1") (pinfunction "1_1") (pintype "passive"))
      (node (ref "C110") (pin "1") (pinfunction "1_1") (pintype "passive"))
      (node (ref "C111") (pin "1") (pinfunction "1_1") (pintype "passive"))
      (node (ref "C112") (pin "1") (pinfunction "1_1") (pintype "passive"))
      (node (ref "FR35") (pin "2") (pinfunction "2_2") (pintype "passive"))
      (node (ref "IC12") (pin "D10") (pinfunction "VCCA2_D10") (pintype "passive"))
      (node (ref "IC12") (pin "D3") (pinfunction "ADC_VREF_D3") (pintype "passive"))
      (node (ref "IC12") (pin "D4") (pinfunction "VCCA3_D4") (pintype "passive"))
      (node (ref "IC12") (pin "K4") (pinfunction "VCCA1_K4") (pintype "passive"))
      (node (ref "IC12") (pin "K9") (pinfunction "VCCA4_K9") (pintype "passive"))
    )
    (net (code "133") (name "VCC5P0") (class "Default")
      (node (ref "J3") (pin "7") (pinfunction "7_7") (pintype "passive"))
      (node (ref "R33") (pin "1") (pinfunction "1_1") (pintype "passive"))
    )
    (net (code "134") (name "unconnected-(IC12A-DIFFOUT_L3n-PadE3)") (class "Default")
      (node (ref "IC12") (pin "E3") (pinfunction "DIFFOUT_L3n_E3") (pintype "bidirectional+no_connect"))
    )
    (net (code "135") (name "unconnected-(IC12A-DIFFOUT_L3p-PadE4)") (class "Default")
      (node (ref "IC12") (pin "E4") (pinfunction "DIFFOUT_L3p_E4") (pintype "bidirectional+no_connect"))
    )
    (net (code "136") (name "unconnected-(J4-Pad6)") (class "Default")
      (node (ref "J4") (pin "6") (pinfunction "6_6") (pintype "passive+no_connect"))
    )
    (net (code "137") (name "unconnected-(J4-Pad7)") (class "Default")
      (node (ref "J4") (pin "7") (pinfunction "7_7") (pintype "passive+no_connect"))
    )
    (net (code "138") (name "unconnected-(J4-Pad8)") (class "Default")
      (node (ref "J4") (pin "8") (pinfunction "8_8") (pintype "passive+no_connect"))
    )
  )
)
